# Sheet2.net
KiCad netlist of a schematic drawn in Altium Designer
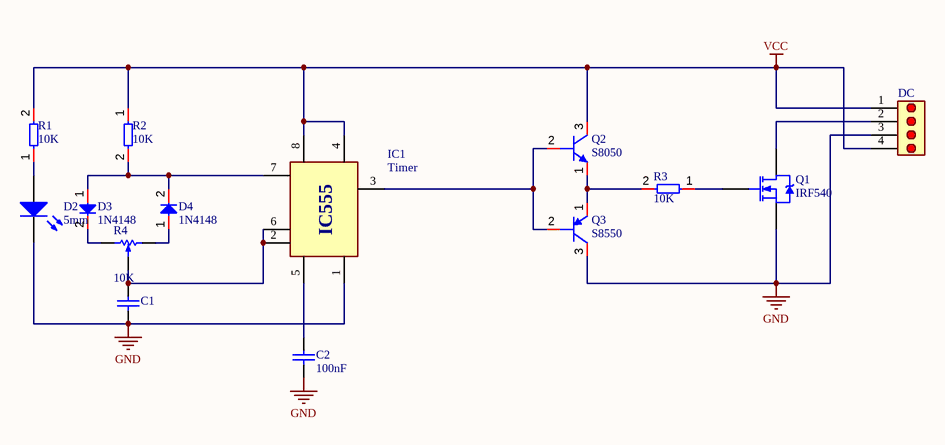
[diagram p0: Sheet2.SchDoc]

(export (version "E")
  (design (tool "Eeschema 10.0.6"))
  (components
    (comp (ref "C1")
      (value "SMD 0603")
      (footprint "SMD CAPACITOR0805")
      (libsource (lib "Library 3D") (part "CAP SMD"))
    )
    (comp (ref "C2")
      (value "100nF")
      (footprint "CN5")
      (fields (field (name "PUBLISHER") "Altium Limited"))
      (libsource (lib "Library 3D") (part "CN 33pF"))
    )
    (comp (ref "D2") (value "5mm") (footprint "LED 5mm BLUE") (libsource (lib "Library 3D") (part "LED 5mm")))
    (comp (ref "D3")
      (value "1N4148")
      (footprint "SOD-80")
      (libsource (lib "SMDLibrary") (part "Diode 1N4148"))
    )
    (comp (ref "D4")
      (value "1N4148")
      (footprint "SOD-80")
      (libsource (lib "SMDLibrary") (part "Diode 1N4148"))
    )
    (comp (ref "DC")
      (value "Header 4")
      (footprint "HEADER 4")
      (libsource (lib "Library 3D") (part "Header 4"))
    )
    (comp (ref "IC1") (value "Timer") (footprint "DIP8") (libsource (lib "Library 3D") (part "555")))
    (comp (ref "Q1") (value "IRF540") (footprint "TO220A") (libsource (lib "Library 3D") (part "IRF540")))
    (comp (ref "Q2") (value "S8050") (footprint "TO-92") (libsource (lib "SMDLibrary") (part "S8050-TO92")))
    (comp (ref "Q3") (value "S8550") (footprint "TO-92") (libsource (lib "SMDLibrary") (part "S8550-TO92")))
    (comp (ref "R1") (value "10K") (footprint "RES-0.25W-H-MF") (libsource (lib "") (part "Resistors THD_2")))
    (comp (ref "R2")
      (value "10K")
      (footprint "RES-0.25W-H-MF")
      (libsource (lib "SMDLibrary") (part "Resistors THD"))
    )
    (comp (ref "R3") (value "10K") (footprint "RES-0.25W-H-MF") (libsource (lib "") (part "Resistors THD_1")))
    (comp (ref "R4") (value "10K") (footprint "VOLUME2") (libsource (lib "Library 3D") (part "Res Variable")))
  )
  (nets
    (net (code "1") (name "GND") (class "Default")
      (node (ref "C1") (pin "1") (pinfunction "1_1") (pintype "passive"))
      (node (ref "C2") (pin "1") (pinfunction "1_1") (pintype "passive"))
      (node (ref "D2") (pin "2") (pinfunction "K_2") (pintype "passive"))
      (node (ref "DC") (pin "3") (pinfunction "3_3") (pintype "passive"))
      (node (ref "IC1") (pin "1") (pinfunction "1_1") (pintype "passive"))
      (node (ref "Q1") (pin "3") (pinfunction "S_3") (pintype "passive"))
      (node (ref "Q3") (pin "3") (pinfunction "C_3") (pintype "passive"))
    )
    (net (code "2") (name "Net-(C2-Pad2)") (class "Default")
      (node (ref "C2") (pin "2") (pinfunction "2_2") (pintype "passive"))
      (node (ref "IC1") (pin "5") (pinfunction "5_5") (pintype "passive"))
    )
    (net (code "3") (name "Net-(D2-A)") (class "Default")
      (node (ref "D2") (pin "1") (pinfunction "A_1") (pintype "passive"))
      (node (ref "R1") (pin "1") (pinfunction "1_1") (pintype "passive"))
    )
    (net (code "4") (name "Net-(D3-Pad1)") (class "Default")
      (node (ref "D3") (pin "1") (pinfunction "1_1") (pintype "passive"))
      (node (ref "D4") (pin "2") (pinfunction "2_2") (pintype "passive"))
      (node (ref "IC1") (pin "7") (pinfunction "7_7") (pintype "passive"))
      (node (ref "R2") (pin "2") (pinfunction "2_2") (pintype "passive"))
    )
    (net (code "5") (name "Net-(Q1-D)") (class "Default")
      (node (ref "DC") (pin "2") (pinfunction "2_2") (pintype "passive"))
      (node (ref "Q1") (pin "2") (pinfunction "D_2") (pintype "passive"))
    )
    (net (code "6") (name "Net-(Q1-G)") (class "Default")
      (node (ref "Q1") (pin "1") (pinfunction "G_1") (pintype "passive"))
      (node (ref "R3") (pin "1") (pinfunction "1_1") (pintype "passive"))
    )
    (net (code "7") (name "Net-(Q2-B)") (class "Default")
      (node (ref "IC1") (pin "3") (pinfunction "3_3") (pintype "passive"))
      (node (ref "Q2") (pin "2") (pinfunction "B_2") (pintype "passive"))
      (node (ref "Q3") (pin "2") (pinfunction "B_2") (pintype "passive"))
    )
    (net (code "8") (name "Net-(Q2-E)") (class "Default")
      (node (ref "Q2") (pin "1") (pinfunction "E_1") (pintype "passive"))
      (node (ref "Q3") (pin "1") (pinfunction "E_1") (pintype "passive"))
      (node (ref "R3") (pin "2") (pinfunction "2_2") (pintype "passive"))
    )
    (net (code "9") (name "Net-(R4-+)") (class "Default")
      (node (ref "D4") (pin "1") (pinfunction "1_1") (pintype "passive"))
      (node (ref "R4") (pin "1") (pinfunction "+_1") (pintype "passive"))
    )
    (net (code "10") (name "Net-(R4--)") (class "Default")
      (node (ref "D3") (pin "2") (pinfunction "2_2") (pintype "passive"))
      (node (ref "R4") (pin "3") (pinfunction "-_3") (pintype "passive"))
    )
    (net (code "11") (name "Net-(R4-W)") (class "Default")
      (node (ref "C1") (pin "2") (pinfunction "2_2") (pintype "passive"))
      (node (ref "IC1") (pin "2") (pinfunction "2_2") (pintype "passive"))
      (node (ref "IC1") (pin "6") (pinfunction "6_6") (pintype "passive"))
      (node (ref "R4") (pin "2") (pinfunction "W_2") (pintype "passive"))
    )
    (net (code "12") (name "VCC") (class "Default")
      (node (ref "DC") (pin "1") (pinfunction "1_1") (pintype "passive"))
      (node (ref "DC") (pin "4") (pinfunction "4_4") (pintype "passive"))
      (node (ref "IC1") (pin "4") (pinfunction "4_4") (pintype "passive"))
      (node (ref "IC1") (pin "8") (pinfunction "8_8") (pintype "passive"))
      (node (ref "Q2") (pin "3") (pinfunction "C_3") (pintype "passive"))
      (node (ref "R1") (pin "2") (pinfunction "2_2") (pintype "passive"))
      (node (ref "R2") (pin "1") (pinfunction "1_1") (pintype "passive"))
    )
  )
)
